# Real_Time_Clock.net
KiCad netlist of a schematic drawn in Altium Designer
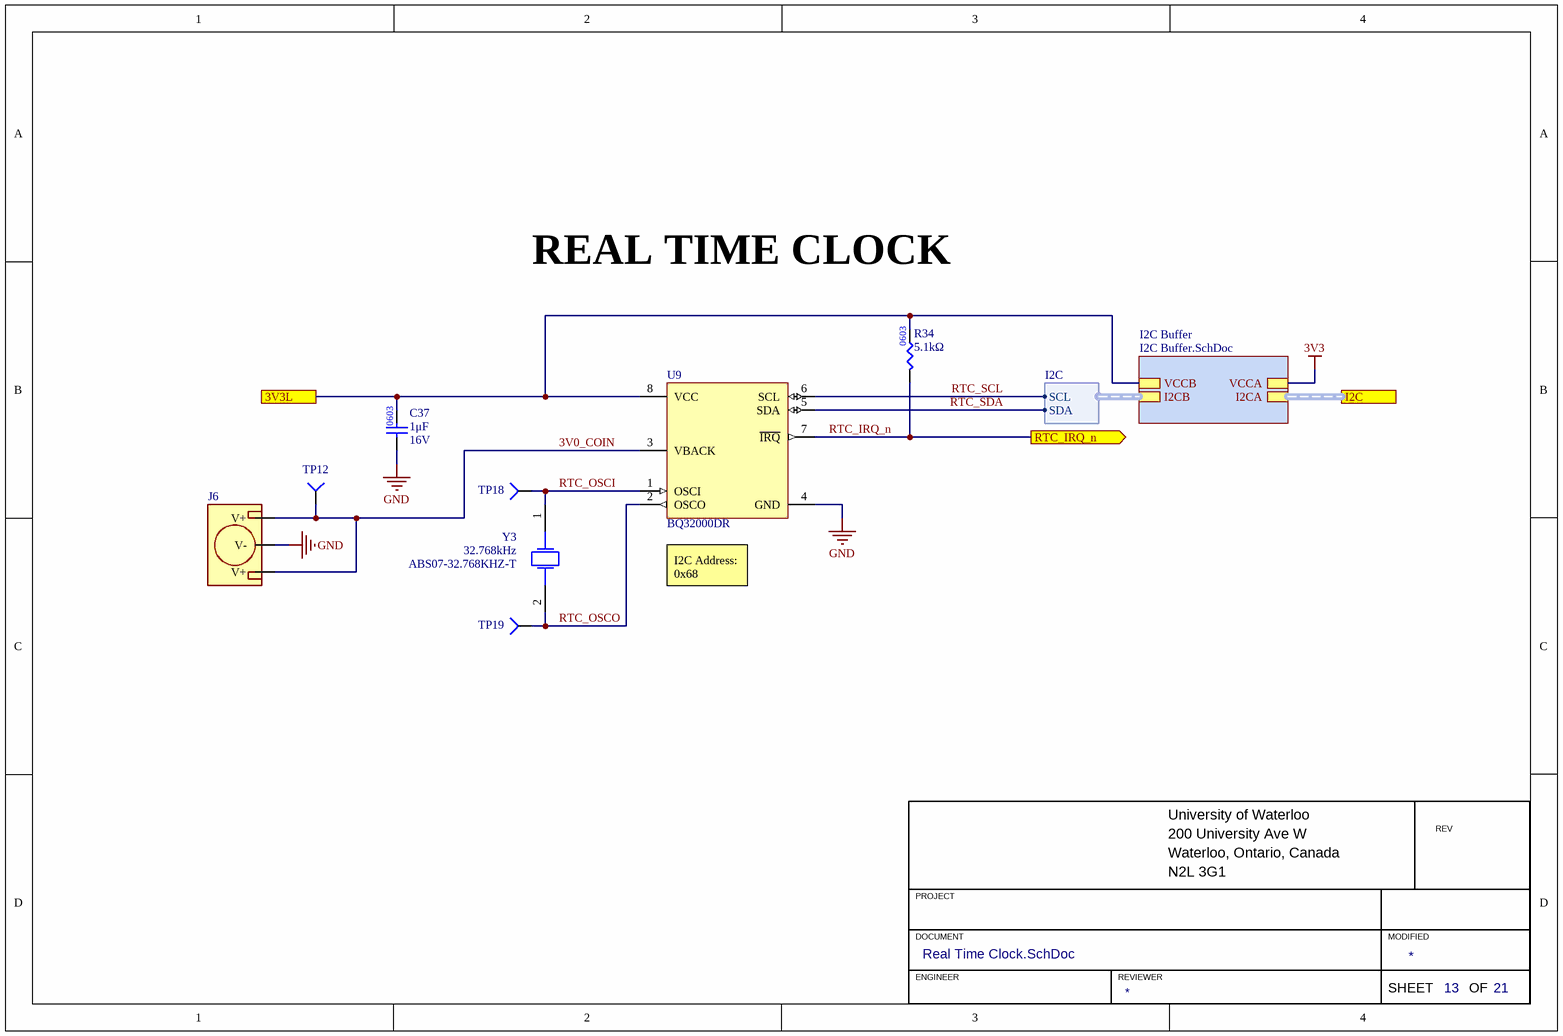
[diagram p0: Real Time Clock.SchDoc]

(export (version "E")
  (design (tool "Eeschema 10.0.6"))
  (components
    (comp (ref "C37")
      (value "1μF")
      (footprint "CAP0603")
      (description "CAP CER 1UF 16V X7R 0603")
      (fields (field (name "VOLTAGE RATING") "16V") (field (name "Comment") "CAP_1uF_16V_0603"))
      (libsource (lib "Personal_Schematic_Library_2022") (part "CAP_1uF_16V_0603"))
    )
    (comp (ref "J6")
      (value "CON_2POS_CR1220")
      (footprint "ATECH_COIN_12MM")
      (description "BATTERY RETAINER COIN 12MM SMD")
      (libsource (lib "Personal_Schematic_Library_2022") (part "CON_2POS_CR1220"))
    )
    (comp (ref "R34")
      (value "5.1kΩ")
      (footprint "RES0603")
      (description "RES 5.1K OHM 1% 1/10W 0603")
      (fields (field (name "Comment") "RES_5.1kΩ_0603_1%"))
      (libsource (lib "Personal_Schematic_Library_2022") (part "RES_5.1kΩ_0603_1%"))
    )
    (comp (ref "TP12")
      (value "TESTPOINT_1MM_CIRCLE")
      (footprint "TESTPOINT_CIRCLE_1MM")
      (description "TESTPOINT 1MM CIRCLE")
      (libsource (lib "Personal_Schematic_Library_2022") (part "TESTPOINT_1MM_CIRCLE"))
    )
    (comp (ref "TP18")
      (value "TESTPOINT_1MM_CIRCLE")
      (footprint "TESTPOINT_CIRCLE_1MM")
      (description "TESTPOINT 1MM CIRCLE")
      (libsource (lib "Personal_Schematic_Library_2022") (part "TESTPOINT_1MM_CIRCLE"))
    )
    (comp (ref "TP19")
      (value "TESTPOINT_1MM_CIRCLE")
      (footprint "TESTPOINT_CIRCLE_1MM")
      (description "TESTPOINT 1MM CIRCLE")
      (libsource (lib "Personal_Schematic_Library_2022") (part "TESTPOINT_1MM_CIRCLE"))
    )
    (comp (ref "U9")
      (value "BQ32000DR")
      (footprint "TI_8-SOIC")
      (description "IC RTC CLK/CALENDAR I2C 8SOIC")
      (libsource (lib "Personal_Schematic_Library_2022") (part "BQ32000DR"))
    )
    (comp (ref "Y3")
      (value "CRYSTAL_32.768KHZ_ABRACON")
      (footprint "OSC_ABS07")
      (description "CRYSTAL 32.7680KHZ 12.5PF SMD")
      (fields
        (field (name "FREQUENCY") "32.768kHz")
        (field (name "MANUFACTURER PART NUMBER 1") "ABS07-32.768KHZ-T")
      )
      (libsource (lib "Personal_Schematic_Library_2022") (part "CRYSTAL_32.768KHZ_ABRACON"))
    )
  )
  (nets
    (net (code "3") (name "/3V0_COIN") (class "Default")
      (node (ref "J6") (pin "1") (pinfunction "V+_1") (pintype "power_in"))
      (node (ref "TP12") (pin "1") (pinfunction "=value_1") (pintype "passive"))
      (node (ref "U9") (pin "3") (pinfunction "VBACK_3") (pintype "power_in"))
    )
    (net (code "4") (name "/3V3L") (class "Default")
      (node (ref "C37") (pin "2") (pinfunction "2_2") (pintype "passive"))
      (node (ref "R34") (pin "2") (pinfunction "2_2") (pintype "passive"))
      (node (ref "U9") (pin "8") (pinfunction "VCC_8") (pintype "power_in"))
    )
    (net (code "6") (name "/RTC_IRQ_n") (class "Default")
      (node (ref "R34") (pin "1") (pinfunction "1_1") (pintype "passive"))
      (node (ref "U9") (pin "7") (pinfunction "~{IRQ}_7") (pintype "output"))
    )
    (net (code "7") (name "/RTC_OSCI") (class "Default")
      (node (ref "TP18") (pin "1") (pinfunction "=value_1") (pintype "passive"))
      (node (ref "U9") (pin "1") (pinfunction "OSCI_1") (pintype "input"))
      (node (ref "Y3") (pin "1") (pinfunction "1_1") (pintype "passive"))
    )
    (net (code "8") (name "/RTC_OSCO") (class "Default")
      (node (ref "TP19") (pin "1") (pinfunction "=value_1") (pintype "passive"))
      (node (ref "U9") (pin "2") (pinfunction "OSCO_2") (pintype "output"))
      (node (ref "Y3") (pin "2") (pinfunction "2_2") (pintype "passive"))
    )
    (net (code "9") (name "/RTC_SCL") (class "Default")
      (node (ref "U9") (pin "6") (pinfunction "SCL_6") (pintype "bidirectional"))
    )
    (net (code "10") (name "/RTC_SDA") (class "Default")
      (node (ref "U9") (pin "5") (pinfunction "SDA_5") (pintype "bidirectional"))
    )
    (net (code "13") (name "GND") (class "Default")
      (node (ref "C37") (pin "1") (pinfunction "1_1") (pintype "passive"))
      (node (ref "J6") (pin "2") (pinfunction "V-_2") (pintype "power_in"))
      (node (ref "U9") (pin "4") (pinfunction "GND_4") (pintype "power_in"))
    )
  )
)
